# miflo.net
KiCad netlist of a schematic drawn in EAGLE
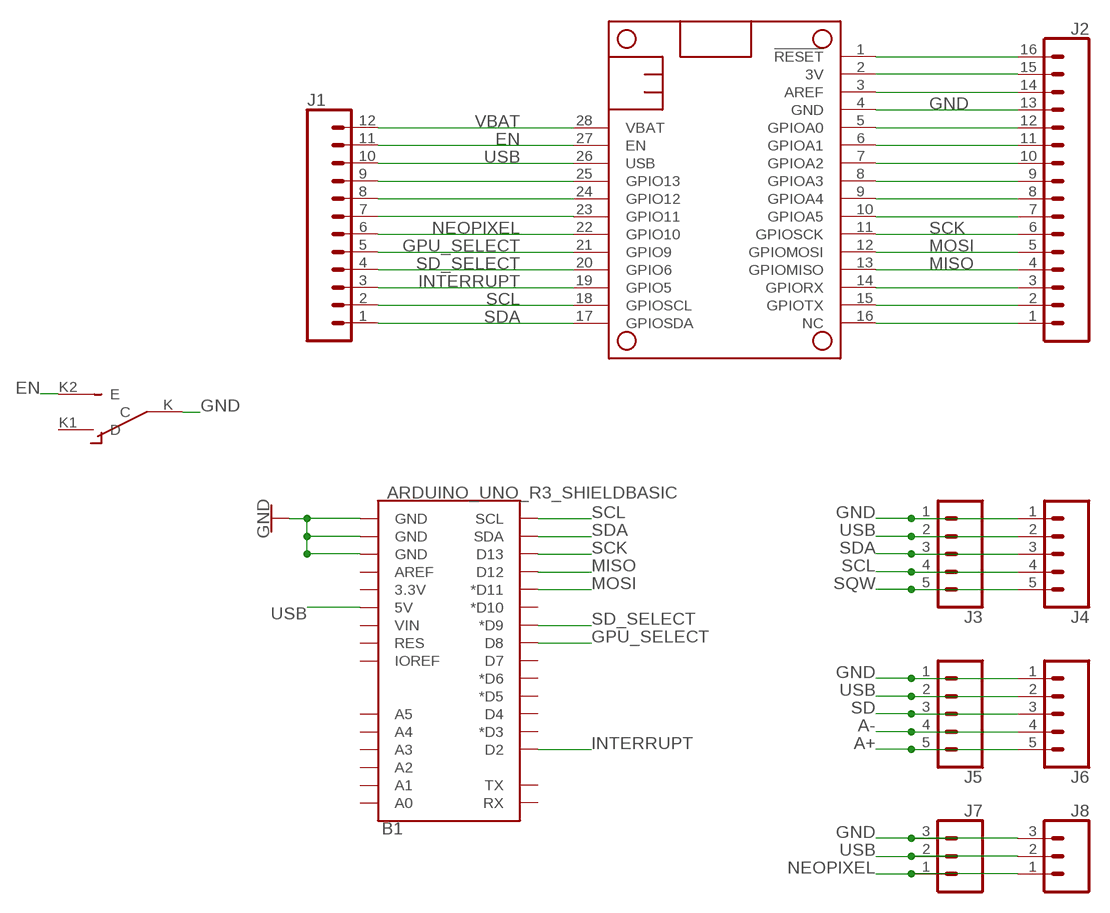
[diagram p0: schematic, sheet 1]

(export (version "E")
  (design (tool "Eeschema 10.0.6"))
  (components
    (comp (ref "B1")
      (value "ARDUINO_UNO_R3_SHIELDBASIC")
      (footprint "eagle-import:UNO_R3_SHIELD")
      (libsource (lib "eagle-import") (part "ARDUINO_UNO_R3_SHIELDBASIC"))
    )
    (comp (ref "J1")
      (value "CONN_12")
      (footprint "eagle-import:1X12")
      (libsource (lib "eagle-import") (part "CONN_12"))
    )
    (comp (ref "J2")
      (value "CONN_16")
      (footprint "eagle-import:1X16")
      (libsource (lib "eagle-import") (part "CONN_16"))
    )
    (comp (ref "J3")
      (value "CONN_05")
      (footprint "eagle-import:1X05")
      (libsource (lib "eagle-import") (part "CONN_05"))
    )
    (comp (ref "J4")
      (value "CONN_05")
      (footprint "eagle-import:1X05")
      (libsource (lib "eagle-import") (part "CONN_05"))
    )
    (comp (ref "J5")
      (value "CONN_05")
      (footprint "eagle-import:1X05")
      (libsource (lib "eagle-import") (part "CONN_05"))
    )
    (comp (ref "J6")
      (value "CONN_05")
      (footprint "eagle-import:1X05")
      (libsource (lib "eagle-import") (part "CONN_05"))
    )
    (comp (ref "J7")
      (value "CONN_03")
      (footprint "eagle-import:1X03")
      (libsource (lib "eagle-import") (part "CONN_03"))
    )
    (comp (ref "J8")
      (value "CONN_03")
      (footprint "eagle-import:1X03")
      (libsource (lib "eagle-import") (part "CONN_03"))
    )
    (comp (ref "MS2")
      (value "FEATHERWING_NODIM")
      (footprint "eagle-import:FEATHERWING_DIM")
      (libsource (lib "eagle-import") (part "FEATHERWING_NODIM"))
    )
    (comp (ref "U$11")
      (value "SLIDE-SWITCH")
      (footprint "eagle-import:SLIDE-SWITCH")
      (libsource (lib "eagle-import") (part "SLIDE-SWITCH"))
    )
  )
  (nets
    (net (code "1") (name "/VBAT") (class "Default")
      (node (ref "J1") (pin "12") (pinfunction "12_12") (pintype "passive"))
      (node (ref "MS2") (pin "28") (pinfunction "VBAT_28") (pintype "power_in"))
    )
    (net (code "2") (name "A+") (class "Default")
      (node (ref "J5") (pin "5") (pinfunction "5_5") (pintype "passive"))
      (node (ref "J6") (pin "5") (pinfunction "5_5") (pintype "passive"))
    )
    (net (code "3") (name "A-") (class "Default")
      (node (ref "J5") (pin "4") (pinfunction "4_4") (pintype "passive"))
      (node (ref "J6") (pin "4") (pinfunction "4_4") (pintype "passive"))
    )
    (net (code "4") (name "EN") (class "Default")
      (node (ref "J1") (pin "11") (pinfunction "11_11") (pintype "passive"))
      (node (ref "MS2") (pin "27") (pinfunction "EN_27") (pintype "passive"))
      (node (ref "U$11") (pin "K2") (pinfunction "E_K2") (pintype "bidirectional"))
    )
    (net (code "5") (name "GND") (class "Default")
      (node (ref "B1") (pin "GND@0") (pinfunction "GND_GND@0") (pintype "bidirectional"))
      (node (ref "B1") (pin "GND@1") (pinfunction "GND_GND@1") (pintype "bidirectional"))
      (node (ref "B1") (pin "GND@2") (pinfunction "GND_GND@2") (pintype "bidirectional"))
      (node (ref "J2") (pin "13") (pinfunction "13_13") (pintype "passive"))
      (node (ref "J3") (pin "1") (pinfunction "1_1") (pintype "passive"))
      (node (ref "J4") (pin "1") (pinfunction "1_1") (pintype "passive"))
      (node (ref "J5") (pin "1") (pinfunction "1_1") (pintype "passive"))
      (node (ref "J6") (pin "1") (pinfunction "1_1") (pintype "passive"))
      (node (ref "J7") (pin "3") (pinfunction "3_3") (pintype "passive"))
      (node (ref "J8") (pin "3") (pinfunction "3_3") (pintype "passive"))
      (node (ref "MS2") (pin "4") (pinfunction "GND_4") (pintype "power_in"))
      (node (ref "U$11") (pin "K") (pinfunction "C_K") (pintype "bidirectional"))
    )
    (net (code "6") (name "GPU_SELECT") (class "Default")
      (node (ref "B1") (pin "D8") (pinfunction "D8_D8") (pintype "bidirectional"))
      (node (ref "J1") (pin "5") (pinfunction "5_5") (pintype "passive"))
      (node (ref "MS2") (pin "21") (pinfunction "GPIO9_21") (pintype "bidirectional"))
    )
    (net (code "7") (name "INTERRUPT") (class "Default")
      (node (ref "B1") (pin "D2") (pinfunction "D2_D2") (pintype "bidirectional"))
      (node (ref "J1") (pin "3") (pinfunction "3_3") (pintype "passive"))
      (node (ref "MS2") (pin "19") (pinfunction "GPIO5_19") (pintype "bidirectional"))
    )
    (net (code "8") (name "MISO") (class "Default")
      (node (ref "B1") (pin "D12") (pinfunction "D12_D12") (pintype "bidirectional"))
      (node (ref "J2") (pin "4") (pinfunction "4_4") (pintype "passive"))
      (node (ref "MS2") (pin "13") (pinfunction "GPIOMISO_13") (pintype "bidirectional"))
    )
    (net (code "9") (name "MOSI") (class "Default")
      (node (ref "B1") (pin "D11") (pinfunction "*D11_D11") (pintype "bidirectional"))
      (node (ref "J2") (pin "5") (pinfunction "5_5") (pintype "passive"))
      (node (ref "MS2") (pin "12") (pinfunction "GPIOMOSI_12") (pintype "bidirectional"))
    )
    (net (code "10") (name "NEOPIXEL") (class "Default")
      (node (ref "J1") (pin "6") (pinfunction "6_6") (pintype "passive"))
      (node (ref "J7") (pin "1") (pinfunction "1_1") (pintype "passive"))
      (node (ref "J8") (pin "1") (pinfunction "1_1") (pintype "passive"))
      (node (ref "MS2") (pin "22") (pinfunction "GPIO10_22") (pintype "bidirectional"))
    )
    (net (code "11") (name "Net-(MS2-3V)") (class "Default")
      (node (ref "J2") (pin "15") (pinfunction "15_15") (pintype "passive"))
      (node (ref "MS2") (pin "2") (pinfunction "3V_2") (pintype "power_in"))
    )
    (net (code "12") (name "Net-(MS2-AREF)") (class "Default")
      (node (ref "J2") (pin "14") (pinfunction "14_14") (pintype "passive"))
      (node (ref "MS2") (pin "3") (pinfunction "AREF_3") (pintype "passive"))
    )
    (net (code "13") (name "Net-(MS2-GPIO11)") (class "Default")
      (node (ref "J1") (pin "7") (pinfunction "7_7") (pintype "passive"))
      (node (ref "MS2") (pin "23") (pinfunction "GPIO11_23") (pintype "bidirectional"))
    )
    (net (code "14") (name "Net-(MS2-GPIO12)") (class "Default")
      (node (ref "J1") (pin "8") (pinfunction "8_8") (pintype "passive"))
      (node (ref "MS2") (pin "24") (pinfunction "GPIO12_24") (pintype "bidirectional"))
    )
    (net (code "15") (name "Net-(MS2-GPIO13)") (class "Default")
      (node (ref "J1") (pin "9") (pinfunction "9_9") (pintype "passive"))
      (node (ref "MS2") (pin "25") (pinfunction "GPIO13_25") (pintype "bidirectional"))
    )
    (net (code "16") (name "Net-(MS2-GPIOA0)") (class "Default")
      (node (ref "J2") (pin "12") (pinfunction "12_12") (pintype "passive"))
      (node (ref "MS2") (pin "5") (pinfunction "GPIOA0_5") (pintype "bidirectional"))
    )
    (net (code "17") (name "Net-(MS2-GPIOA1)") (class "Default")
      (node (ref "J2") (pin "11") (pinfunction "11_11") (pintype "passive"))
      (node (ref "MS2") (pin "6") (pinfunction "GPIOA1_6") (pintype "bidirectional"))
    )
    (net (code "18") (name "Net-(MS2-GPIOA2)") (class "Default")
      (node (ref "J2") (pin "10") (pinfunction "10_10") (pintype "passive"))
      (node (ref "MS2") (pin "7") (pinfunction "GPIOA2_7") (pintype "bidirectional"))
    )
    (net (code "19") (name "Net-(MS2-GPIOA3)") (class "Default")
      (node (ref "J2") (pin "9") (pinfunction "9_9") (pintype "passive"))
      (node (ref "MS2") (pin "8") (pinfunction "GPIOA3_8") (pintype "bidirectional"))
    )
    (net (code "20") (name "Net-(MS2-GPIOA4)") (class "Default")
      (node (ref "J2") (pin "8") (pinfunction "8_8") (pintype "passive"))
      (node (ref "MS2") (pin "9") (pinfunction "GPIOA4_9") (pintype "bidirectional"))
    )
    (net (code "21") (name "Net-(MS2-GPIOA5)") (class "Default")
      (node (ref "J2") (pin "7") (pinfunction "7_7") (pintype "passive"))
      (node (ref "MS2") (pin "10") (pinfunction "GPIOA5_10") (pintype "bidirectional"))
    )
    (net (code "22") (name "Net-(MS2-GPIORX)") (class "Default")
      (node (ref "J2") (pin "3") (pinfunction "3_3") (pintype "passive"))
      (node (ref "MS2") (pin "14") (pinfunction "GPIORX_14") (pintype "bidirectional"))
    )
    (net (code "23") (name "Net-(MS2-GPIOTX)") (class "Default")
      (node (ref "J2") (pin "2") (pinfunction "2_2") (pintype "passive"))
      (node (ref "MS2") (pin "15") (pinfunction "GPIOTX_15") (pintype "bidirectional"))
    )
    (net (code "24") (name "Net-(MS2-NC)") (class "Default")
      (node (ref "J2") (pin "1") (pinfunction "1_1") (pintype "passive"))
      (node (ref "MS2") (pin "16") (pinfunction "NC_16") (pintype "passive"))
    )
    (net (code "25") (name "Net-(MS2-~{RESET})") (class "Default")
      (node (ref "J2") (pin "16") (pinfunction "16_16") (pintype "passive"))
      (node (ref "MS2") (pin "1") (pinfunction "~{RESET}_1") (pintype "input"))
    )
    (net (code "26") (name "SCK") (class "Default")
      (node (ref "B1") (pin "D13") (pinfunction "D13_D13") (pintype "bidirectional"))
      (node (ref "J2") (pin "6") (pinfunction "6_6") (pintype "passive"))
      (node (ref "MS2") (pin "11") (pinfunction "GPIOSCK_11") (pintype "bidirectional"))
    )
    (net (code "27") (name "SCL") (class "Default")
      (node (ref "B1") (pin "SCL") (pinfunction "SCL_SCL") (pintype "bidirectional"))
      (node (ref "J1") (pin "2") (pinfunction "2_2") (pintype "passive"))
      (node (ref "J3") (pin "4") (pinfunction "4_4") (pintype "passive"))
      (node (ref "J4") (pin "4") (pinfunction "4_4") (pintype "passive"))
      (node (ref "MS2") (pin "18") (pinfunction "GPIOSCL_18") (pintype "bidirectional"))
    )
    (net (code "28") (name "SD") (class "Default")
      (node (ref "J5") (pin "3") (pinfunction "3_3") (pintype "passive"))
      (node (ref "J6") (pin "3") (pinfunction "3_3") (pintype "passive"))
    )
    (net (code "29") (name "SDA") (class "Default")
      (node (ref "B1") (pin "SDA") (pinfunction "SDA_SDA") (pintype "bidirectional"))
      (node (ref "J1") (pin "1") (pinfunction "1_1") (pintype "passive"))
      (node (ref "J3") (pin "3") (pinfunction "3_3") (pintype "passive"))
      (node (ref "J4") (pin "3") (pinfunction "3_3") (pintype "passive"))
      (node (ref "MS2") (pin "17") (pinfunction "GPIOSDA_17") (pintype "bidirectional"))
    )
    (net (code "30") (name "SD_SELECT") (class "Default")
      (node (ref "B1") (pin "D9") (pinfunction "*D9_D9") (pintype "bidirectional"))
      (node (ref "J1") (pin "4") (pinfunction "4_4") (pintype "passive"))
      (node (ref "MS2") (pin "20") (pinfunction "GPIO6_20") (pintype "bidirectional"))
    )
    (net (code "31") (name "SQW") (class "Default")
      (node (ref "J3") (pin "5") (pinfunction "5_5") (pintype "passive"))
      (node (ref "J4") (pin "5") (pinfunction "5_5") (pintype "passive"))
    )
    (net (code "32") (name "USB") (class "Default")
      (node (ref "B1") (pin "5V") (pinfunction "5V_5V") (pintype "bidirectional"))
      (node (ref "J1") (pin "10") (pinfunction "10_10") (pintype "passive"))
      (node (ref "J3") (pin "2") (pinfunction "2_2") (pintype "passive"))
      (node (ref "J4") (pin "2") (pinfunction "2_2") (pintype "passive"))
      (node (ref "J5") (pin "2") (pinfunction "2_2") (pintype "passive"))
      (node (ref "J6") (pin "2") (pinfunction "2_2") (pintype "passive"))
      (node (ref "J7") (pin "2") (pinfunction "2_2") (pintype "passive"))
      (node (ref "J8") (pin "2") (pinfunction "2_2") (pintype "passive"))
      (node (ref "MS2") (pin "26") (pinfunction "USB_26") (pintype "power_in"))
    )
    (net (code "33") (name "unconnected-(B1-*D3-PadD3)") (class "Default")
      (node (ref "B1") (pin "D3") (pinfunction "*D3_D3") (pintype "bidirectional"))
    )
    (net (code "34") (name "unconnected-(B1-*D5-PadD5)") (class "Default")
      (node (ref "B1") (pin "D5") (pinfunction "*D5_D5") (pintype "bidirectional"))
    )
    (net (code "35") (name "unconnected-(B1-*D6-PadD6)") (class "Default")
      (node (ref "B1") (pin "D6") (pinfunction "*D6_D6") (pintype "bidirectional"))
    )
    (net (code "36") (name "unconnected-(B1-*D10-PadD10)") (class "Default")
      (node (ref "B1") (pin "D10") (pinfunction "*D10_D10") (pintype "bidirectional"))
    )
    (net (code "37") (name "unconnected-(B1-Pad3.3V)") (class "Default")
      (node (ref "B1") (pin "3.3V") (pinfunction "3.3V_3.3V") (pintype "bidirectional"))
    )
    (net (code "38") (name "unconnected-(B1-PadA0)") (class "Default")
      (node (ref "B1") (pin "A0") (pinfunction "A0_A0") (pintype "bidirectional"))
    )
    (net (code "39") (name "unconnected-(B1-PadA1)") (class "Default")
      (node (ref "B1") (pin "A1") (pinfunction "A1_A1") (pintype "bidirectional"))
    )
    (net (code "40") (name "unconnected-(B1-PadA2)") (class "Default")
      (node (ref "B1") (pin "A2") (pinfunction "A2_A2") (pintype "bidirectional"))
    )
    (net (code "41") (name "unconnected-(B1-PadA3)") (class "Default")
      (node (ref "B1") (pin "A3") (pinfunction "A3_A3") (pintype "bidirectional"))
    )
    (net (code "42") (name "unconnected-(B1-PadA4)") (class "Default")
      (node (ref "B1") (pin "A4") (pinfunction "A4_A4") (pintype "bidirectional"))
    )
    (net (code "43") (name "unconnected-(B1-PadA5)") (class "Default")
      (node (ref "B1") (pin "A5") (pinfunction "A5_A5") (pintype "bidirectional"))
    )
    (net (code "44") (name "unconnected-(B1-PadAREF)") (class "Default")
      (node (ref "B1") (pin "AREF") (pinfunction "AREF_AREF") (pintype "bidirectional"))
    )
    (net (code "45") (name "unconnected-(B1-PadD4)") (class "Default")
      (node (ref "B1") (pin "D4") (pinfunction "D4_D4") (pintype "bidirectional"))
    )
    (net (code "46") (name "unconnected-(B1-PadD7)") (class "Default")
      (node (ref "B1") (pin "D7") (pinfunction "D7_D7") (pintype "bidirectional"))
    )
    (net (code "47") (name "unconnected-(B1-PadIOREF)") (class "Default")
      (node (ref "B1") (pin "IOREF") (pinfunction "IOREF_IOREF") (pintype "bidirectional"))
    )
    (net (code "48") (name "unconnected-(B1-PadRES)") (class "Default")
      (node (ref "B1") (pin "RES") (pinfunction "RES_RES") (pintype "bidirectional"))
    )
    (net (code "49") (name "unconnected-(B1-PadRX)") (class "Default")
      (node (ref "B1") (pin "RX") (pinfunction "RX_RX") (pintype "bidirectional"))
    )
    (net (code "50") (name "unconnected-(B1-PadTX)") (class "Default")
      (node (ref "B1") (pin "TX") (pinfunction "TX_TX") (pintype "bidirectional"))
    )
    (net (code "51") (name "unconnected-(B1-PadVIN)") (class "Default")
      (node (ref "B1") (pin "VIN") (pinfunction "VIN_VIN") (pintype "bidirectional"))
    )
    (net (code "52") (name "unconnected-(U$11-D-PadK1)") (class "Default")
      (node (ref "U$11") (pin "K1") (pinfunction "D_K1") (pintype "bidirectional"))
    )
  )
)
